# schematicEagle.net
KiCad netlist of a schematic drawn in EAGLE
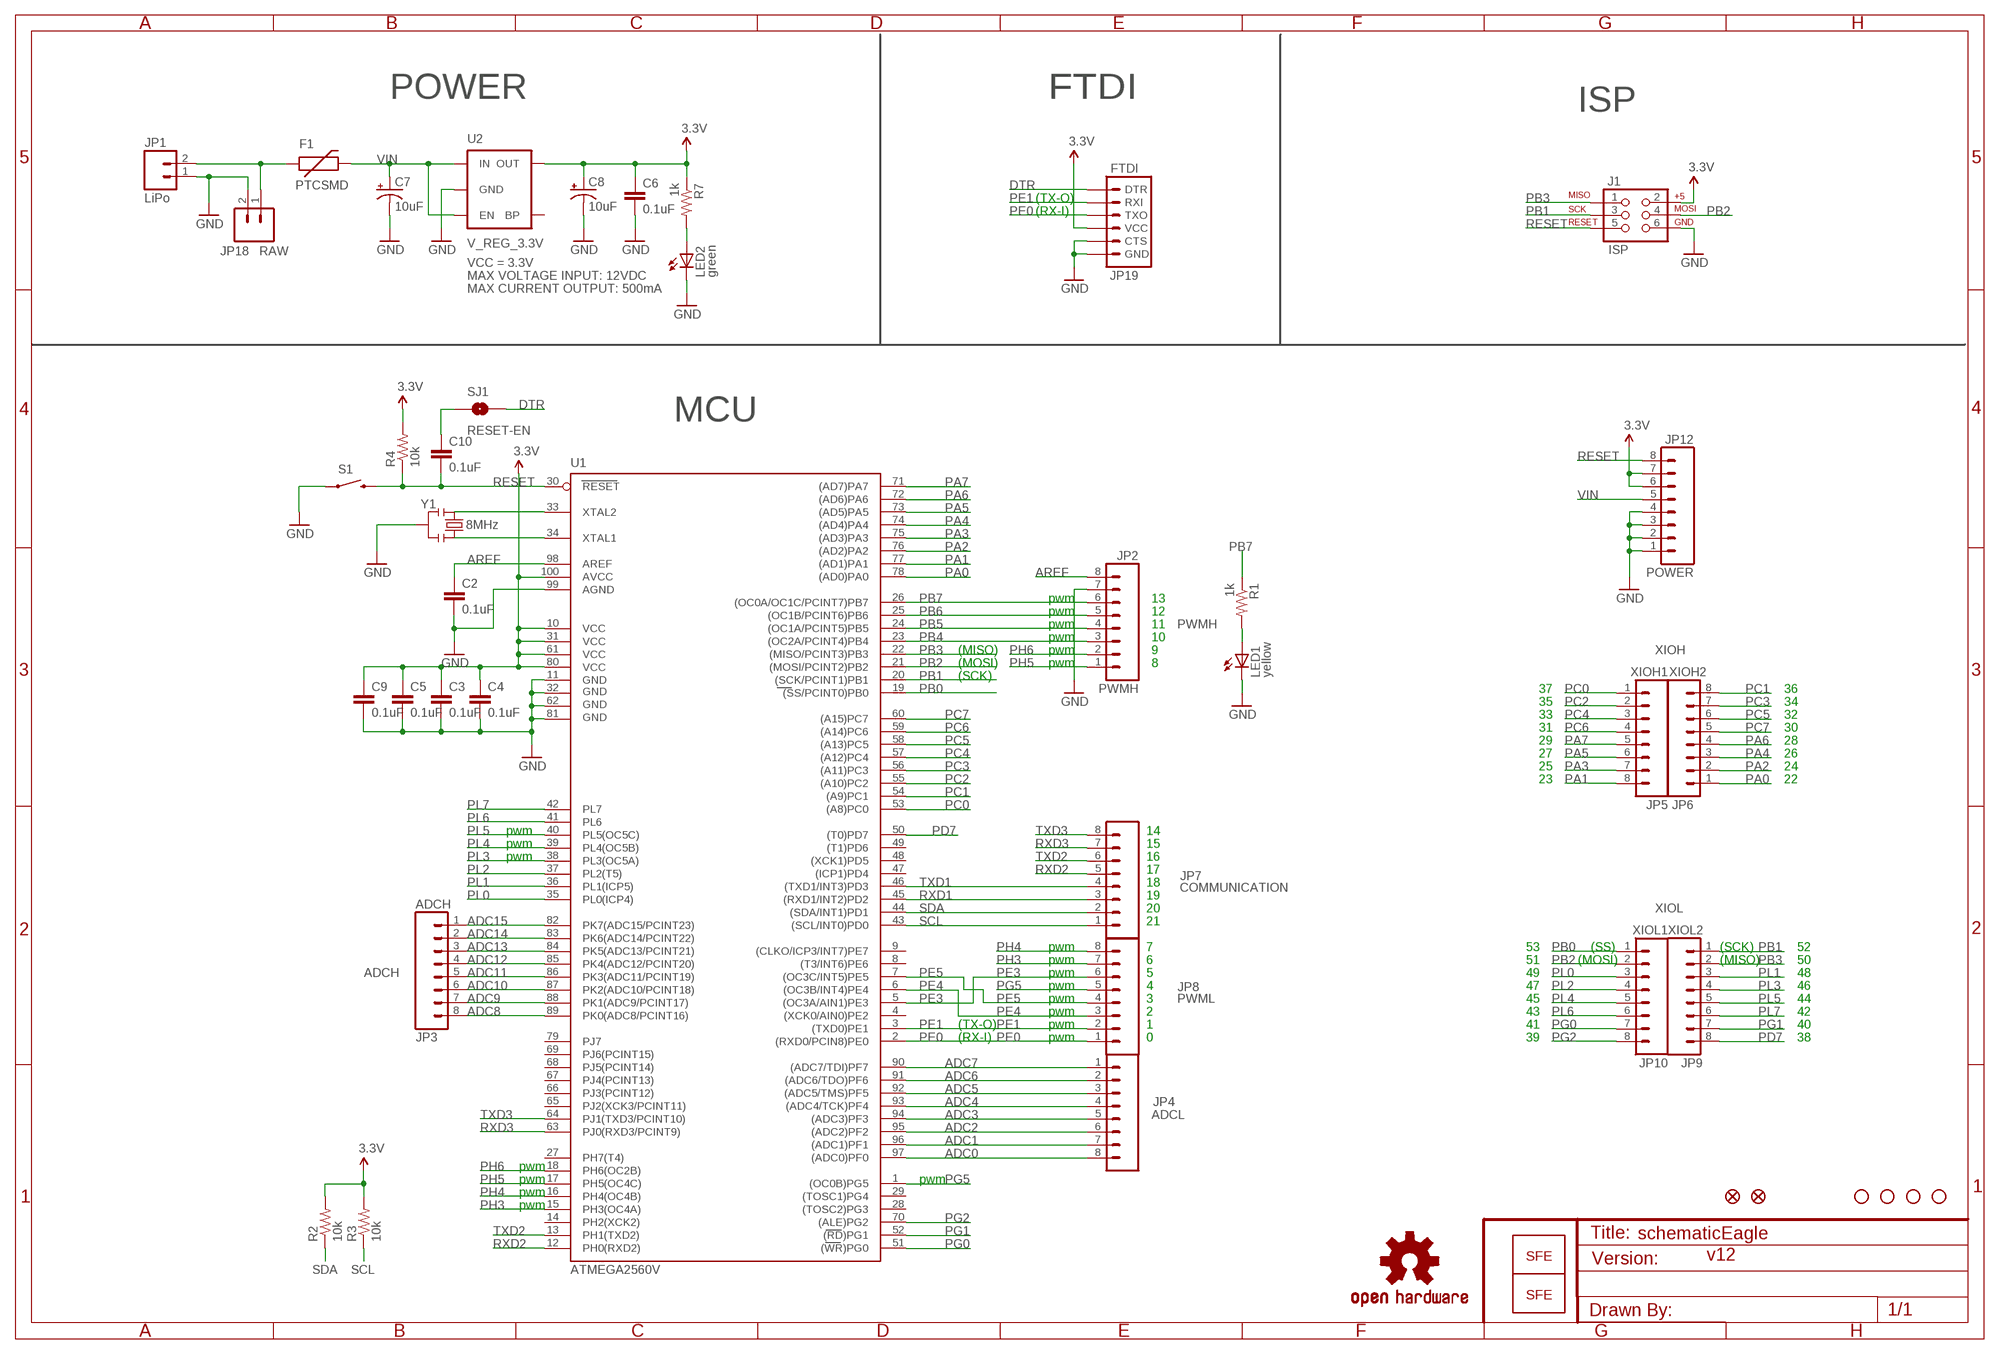
[diagram p0: schematic, sheet 1]

(export (version "E")
  (design (tool "Eeschema 10.0.6"))
  (components
    (comp (ref "C2")
      (value "0.1uF")
      (footprint "eagle-import:0402-CAP")
      (libsource (lib "eagle-import") (part "CAP0402-CAP"))
    )
    (comp (ref "C3")
      (value "0.1uF")
      (footprint "eagle-import:0402-CAP")
      (libsource (lib "eagle-import") (part "CAP0402-CAP"))
    )
    (comp (ref "C4")
      (value "0.1uF")
      (footprint "eagle-import:0402-CAP")
      (libsource (lib "eagle-import") (part "CAP0402-CAP"))
    )
    (comp (ref "C5")
      (value "0.1uF")
      (footprint "eagle-import:0402-CAP")
      (libsource (lib "eagle-import") (part "CAP0402-CAP"))
    )
    (comp (ref "C6")
      (value "0.1uF")
      (footprint "eagle-import:0402-CAP")
      (libsource (lib "eagle-import") (part "CAP0402-CAP"))
    )
    (comp (ref "C7")
      (value "10uF")
      (footprint "eagle-import:EIA3216")
      (libsource (lib "eagle-import") (part "CAP_POL1206"))
    )
    (comp (ref "C8")
      (value "10uF")
      (footprint "eagle-import:EIA3216")
      (libsource (lib "eagle-import") (part "CAP_POL1206"))
    )
    (comp (ref "C9")
      (value "0.1uF")
      (footprint "eagle-import:0402-CAP")
      (libsource (lib "eagle-import") (part "CAP0402-CAP"))
    )
    (comp (ref "C10")
      (value "0.1uF")
      (footprint "eagle-import:0402-CAP")
      (libsource (lib "eagle-import") (part "CAP0402-CAP"))
    )
    (comp (ref "F1")
      (value "PTCSMD")
      (footprint "eagle-import:PTC-1206")
      (libsource (lib "eagle-import") (part "PTCSMD"))
    )
    (comp (ref "J1")
      (value "ISP")
      (footprint "eagle-import:2X3")
      (libsource (lib "eagle-import") (part "AVR_SPI_PRG_6PTH"))
    )
    (comp (ref "JP1")
      (value "LiPo")
      (footprint "eagle-import:JST-2-SMD")
      (libsource (lib "eagle-import") (part "M02-JST-2MM-SMT"))
    )
    (comp (ref "JP2")
      (value "PWMH")
      (footprint "eagle-import:BM08B-SRSS-TB")
      (libsource (lib "eagle-import") (part "M08BM08B-SRSS-TB"))
    )
    (comp (ref "JP3")
      (value "ADCH")
      (footprint "eagle-import:BM08B-SRSS-TB")
      (libsource (lib "eagle-import") (part "M08BM08B-SRSS-TB"))
    )
    (comp (ref "JP4")
      (value "ADCL")
      (footprint "eagle-import:BM08B-SRSS-TB")
      (libsource (lib "eagle-import") (part "M08BM08B-SRSS-TB"))
    )
    (comp (ref "JP5")
      (value "XIOH1")
      (footprint "eagle-import:BM08B-SRSS-TB")
      (libsource (lib "eagle-import") (part "M08BM08B-SRSS-TB"))
    )
    (comp (ref "JP6")
      (value "XIOH2")
      (footprint "eagle-import:BM08B-SRSS-TB")
      (libsource (lib "eagle-import") (part "M08BM08B-SRSS-TB"))
    )
    (comp (ref "JP7")
      (value "COMM")
      (footprint "eagle-import:BM08B-SRSS-TB")
      (libsource (lib "eagle-import") (part "M08BM08B-SRSS-TB"))
    )
    (comp (ref "JP8")
      (value "PWML")
      (footprint "eagle-import:BM08B-SRSS-TB")
      (libsource (lib "eagle-import") (part "M08BM08B-SRSS-TB"))
    )
    (comp (ref "JP9")
      (value "XIOL2")
      (footprint "eagle-import:BM08B-SRSS-TB")
      (libsource (lib "eagle-import") (part "M08BM08B-SRSS-TB"))
    )
    (comp (ref "JP10")
      (value "XIOL1")
      (footprint "eagle-import:BM08B-SRSS-TB")
      (libsource (lib "eagle-import") (part "M08BM08B-SRSS-TB"))
    )
    (comp (ref "JP11")
      (value "STAND-OFF")
      (footprint "eagle-import:STAND-OFF")
      (libsource (lib "eagle-import") (part "STAND-OFF"))
    )
    (comp (ref "JP12")
      (value "POWER")
      (footprint "eagle-import:BM08B-SRSS-TB")
      (libsource (lib "eagle-import") (part "M08BM08B-SRSS-TB"))
    )
    (comp (ref "JP13")
      (value "STAND-OFF")
      (footprint "eagle-import:STAND-OFF")
      (libsource (lib "eagle-import") (part "STAND-OFF"))
    )
    (comp (ref "JP14")
      (value "STAND-OFF")
      (footprint "eagle-import:STAND-OFF")
      (libsource (lib "eagle-import") (part "STAND-OFF"))
    )
    (comp (ref "JP15")
      (value "STAND-OFF")
      (footprint "eagle-import:STAND-OFF")
      (libsource (lib "eagle-import") (part "STAND-OFF"))
    )
    (comp (ref "JP16")
      (value "LOGO-SFENEW")
      (footprint "eagle-import:SFE-NEW-WEBLOGO")
      (libsource (lib "eagle-import") (part "LOGO-SFENEW"))
    )
    (comp (ref "JP17")
      (value "LOGO-SFESK")
      (footprint "eagle-import:SFE-LOGO-FLAME")
      (libsource (lib "eagle-import") (part "LOGO-SFESK"))
    )
    (comp (ref "JP18")
      (value "RAW")
      (footprint "eagle-import:1X02")
      (libsource (lib "eagle-import") (part "M02PTH"))
    )
    (comp (ref "JP19")
      (value "FTDI")
      (footprint "eagle-import:1X06-SMD")
      (libsource (lib "eagle-import") (part "ARDUINO_SERIAL_PROGRAMSMD"))
    )
    (comp (ref "JP20")
      (value "FIDUCIAL1X2.5")
      (footprint "eagle-import:FIDUCIAL-1X2.5")
      (libsource (lib "eagle-import") (part "FIDUCIAL1X2.5"))
    )
    (comp (ref "JP21")
      (value "FIDUCIAL1X2.5")
      (footprint "eagle-import:FIDUCIAL-1X2.5")
      (libsource (lib "eagle-import") (part "FIDUCIAL1X2.5"))
    )
    (comp (ref "LED1")
      (value "yellow")
      (footprint "eagle-import:LED-0603")
      (libsource (lib "eagle-import") (part "LED0603"))
    )
    (comp (ref "LED2")
      (value "green")
      (footprint "eagle-import:LED-0603")
      (libsource (lib "eagle-import") (part "LED0603"))
    )
    (comp (ref "R1")
      (value "1k")
      (footprint "eagle-import:0402-RES")
      (libsource (lib "eagle-import") (part "RESISTOR0402-RES"))
    )
    (comp (ref "R2")
      (value "10k")
      (footprint "eagle-import:0402-RES")
      (libsource (lib "eagle-import") (part "RESISTOR0402-RES"))
    )
    (comp (ref "R3")
      (value "10k")
      (footprint "eagle-import:0402-RES")
      (libsource (lib "eagle-import") (part "RESISTOR0402-RES"))
    )
    (comp (ref "R4")
      (value "10k")
      (footprint "eagle-import:0402-RES")
      (libsource (lib "eagle-import") (part "RESISTOR0402-RES"))
    )
    (comp (ref "R7")
      (value "1k")
      (footprint "eagle-import:0402-RES")
      (libsource (lib "eagle-import") (part "RESISTOR0402-RES"))
    )
    (comp (ref "S1")
      (value "SWITCH-MOMENTARY-2SMD")
      (footprint "eagle-import:TACTILE_SWITCH_SMD")
      (libsource (lib "eagle-import") (part "SWITCH-MOMENTARY-2SMD"))
    )
    (comp (ref "SJ1")
      (value "RESET-EN")
      (footprint "eagle-import:SJ_2S")
      (libsource (lib "eagle-import") (part "SOLDERJUMPERNC"))
    )
    (comp (ref "U$9")
      (value "OSHW-LOGOL")
      (footprint "eagle-import:OSHW-LOGO-L")
      (libsource (lib "eagle-import") (part "OSHW-LOGOL"))
    )
    (comp (ref "U1")
      (value "ATMEGA2560AU")
      (footprint "eagle-import:TQFP100")
      (libsource (lib "eagle-import") (part "ATMEGA2560AU"))
    )
    (comp (ref "U2")
      (value "V_REG_3.3V")
      (footprint "eagle-import:SOT23-5")
      (libsource (lib "eagle-import") (part "V_REG_LDOSMD"))
    )
    (comp (ref "Y1")
      (value "RESONATORSMD")
      (footprint "eagle-import:RESONATOR-SMD")
      (libsource (lib "eagle-import") (part "RESONATORSMD"))
    )
  )
  (nets
    (net (code "1") (name "/ADC0") (class "Default")
      (node (ref "JP4") (pin "8") (pinfunction "8_8") (pintype "passive"))
      (node (ref "U1") (pin "97") (pinfunction "(ADC0)PF0_97") (pintype "bidirectional"))
    )
    (net (code "2") (name "/ADC1") (class "Default")
      (node (ref "JP4") (pin "7") (pinfunction "7_7") (pintype "passive"))
      (node (ref "U1") (pin "96") (pinfunction "(ADC1)PF1_96") (pintype "bidirectional"))
    )
    (net (code "3") (name "/ADC2") (class "Default")
      (node (ref "JP4") (pin "6") (pinfunction "6_6") (pintype "passive"))
      (node (ref "U1") (pin "95") (pinfunction "(ADC2)PF2_95") (pintype "bidirectional"))
    )
    (net (code "4") (name "/ADC3") (class "Default")
      (node (ref "JP4") (pin "5") (pinfunction "5_5") (pintype "passive"))
      (node (ref "U1") (pin "94") (pinfunction "(ADC3)PF3_94") (pintype "bidirectional"))
    )
    (net (code "5") (name "/ADC4") (class "Default")
      (node (ref "JP4") (pin "4") (pinfunction "4_4") (pintype "passive"))
      (node (ref "U1") (pin "93") (pinfunction "(ADC4/TCK)PF4_93") (pintype "bidirectional"))
    )
    (net (code "6") (name "/ADC5") (class "Default")
      (node (ref "JP4") (pin "3") (pinfunction "3_3") (pintype "passive"))
      (node (ref "U1") (pin "92") (pinfunction "(ADC5/TMS)PF5_92") (pintype "bidirectional"))
    )
    (net (code "7") (name "/ADC6") (class "Default")
      (node (ref "JP4") (pin "2") (pinfunction "2_2") (pintype "passive"))
      (node (ref "U1") (pin "91") (pinfunction "(ADC6/TDO)PF6_91") (pintype "bidirectional"))
    )
    (net (code "8") (name "/ADC7") (class "Default")
      (node (ref "JP4") (pin "1") (pinfunction "1_1") (pintype "passive"))
      (node (ref "U1") (pin "90") (pinfunction "(ADC7/TDI)PF7_90") (pintype "bidirectional"))
    )
    (net (code "9") (name "/ADC8") (class "Default")
      (node (ref "JP3") (pin "8") (pinfunction "8_8") (pintype "passive"))
      (node (ref "U1") (pin "89") (pinfunction "PK0(ADC8/PCINT16)_89") (pintype "bidirectional"))
    )
    (net (code "10") (name "/ADC9") (class "Default")
      (node (ref "JP3") (pin "7") (pinfunction "7_7") (pintype "passive"))
      (node (ref "U1") (pin "88") (pinfunction "PK1(ADC9/PCINT17)_88") (pintype "bidirectional"))
    )
    (net (code "11") (name "/ADC10") (class "Default")
      (node (ref "JP3") (pin "6") (pinfunction "6_6") (pintype "passive"))
      (node (ref "U1") (pin "87") (pinfunction "PK2(ADC10/PCINT18)_87") (pintype "bidirectional"))
    )
    (net (code "12") (name "/ADC11") (class "Default")
      (node (ref "JP3") (pin "5") (pinfunction "5_5") (pintype "passive"))
      (node (ref "U1") (pin "86") (pinfunction "PK3(ADC11/PCINT19)_86") (pintype "bidirectional"))
    )
    (net (code "13") (name "/ADC12") (class "Default")
      (node (ref "JP3") (pin "4") (pinfunction "4_4") (pintype "passive"))
      (node (ref "U1") (pin "85") (pinfunction "PK4(ADC12/PCINT20)_85") (pintype "bidirectional"))
    )
    (net (code "14") (name "/ADC13") (class "Default")
      (node (ref "JP3") (pin "3") (pinfunction "3_3") (pintype "passive"))
      (node (ref "U1") (pin "84") (pinfunction "PK5(ADC13/PCINT21)_84") (pintype "bidirectional"))
    )
    (net (code "15") (name "/ADC14") (class "Default")
      (node (ref "JP3") (pin "2") (pinfunction "2_2") (pintype "passive"))
      (node (ref "U1") (pin "83") (pinfunction "PK6(ADC14/PCINT22)_83") (pintype "bidirectional"))
    )
    (net (code "16") (name "/ADC15") (class "Default")
      (node (ref "JP3") (pin "1") (pinfunction "1_1") (pintype "passive"))
      (node (ref "U1") (pin "82") (pinfunction "PK7(ADC15/PCINT23)_82") (pintype "bidirectional"))
    )
    (net (code "17") (name "/AREF") (class "Default")
      (node (ref "C2") (pin "1") (pinfunction "1_1") (pintype "passive"))
      (node (ref "JP2") (pin "8") (pinfunction "8_8") (pintype "passive"))
      (node (ref "U1") (pin "98") (pinfunction "AREF_98") (pintype "bidirectional"))
    )
    (net (code "18") (name "/DTR") (class "Default")
      (node (ref "JP19") (pin "1") (pinfunction "DTR_1") (pintype "passive"))
      (node (ref "SJ1") (pin "2") (pinfunction "2_2") (pintype "passive"))
    )
    (net (code "19") (name "/PA0") (class "Default")
      (node (ref "JP6") (pin "1") (pinfunction "1_1") (pintype "passive"))
      (node (ref "U1") (pin "78") (pinfunction "(AD0)PA0_78") (pintype "bidirectional"))
    )
    (net (code "20") (name "/PA1") (class "Default")
      (node (ref "JP5") (pin "8") (pinfunction "8_8") (pintype "passive"))
      (node (ref "U1") (pin "77") (pinfunction "(AD1)PA1_77") (pintype "bidirectional"))
    )
    (net (code "21") (name "/PA2") (class "Default")
      (node (ref "JP6") (pin "2") (pinfunction "2_2") (pintype "passive"))
      (node (ref "U1") (pin "76") (pinfunction "(AD2)PA2_76") (pintype "bidirectional"))
    )
    (net (code "22") (name "/PA3") (class "Default")
      (node (ref "JP5") (pin "7") (pinfunction "7_7") (pintype "passive"))
      (node (ref "U1") (pin "75") (pinfunction "(AD3)PA3_75") (pintype "bidirectional"))
    )
    (net (code "23") (name "/PA4") (class "Default")
      (node (ref "JP6") (pin "3") (pinfunction "3_3") (pintype "passive"))
      (node (ref "U1") (pin "74") (pinfunction "(AD4)PA4_74") (pintype "bidirectional"))
    )
    (net (code "24") (name "/PA5") (class "Default")
      (node (ref "JP5") (pin "6") (pinfunction "6_6") (pintype "passive"))
      (node (ref "U1") (pin "73") (pinfunction "(AD5)PA5_73") (pintype "bidirectional"))
    )
    (net (code "25") (name "/PA6") (class "Default")
      (node (ref "JP6") (pin "4") (pinfunction "4_4") (pintype "passive"))
      (node (ref "U1") (pin "72") (pinfunction "(AD6)PA6_72") (pintype "bidirectional"))
    )
    (net (code "26") (name "/PA7") (class "Default")
      (node (ref "JP5") (pin "5") (pinfunction "5_5") (pintype "passive"))
      (node (ref "U1") (pin "71") (pinfunction "(AD7)PA7_71") (pintype "bidirectional"))
    )
    (net (code "27") (name "/PB0") (class "Default")
      (node (ref "JP10") (pin "1") (pinfunction "1_1") (pintype "passive"))
      (node (ref "U1") (pin "19") (pinfunction "(SS/PCINT0)PB0_19") (pintype "bidirectional"))
    )
    (net (code "28") (name "/PB1") (class "Default")
      (node (ref "J1") (pin "3") (pinfunction "3_3") (pintype "passive"))
      (node (ref "JP9") (pin "1") (pinfunction "1_1") (pintype "passive"))
      (node (ref "U1") (pin "20") (pinfunction "(SCK/PCINT1)PB1_20") (pintype "bidirectional"))
    )
    (net (code "29") (name "/PB2") (class "Default")
      (node (ref "J1") (pin "4") (pinfunction "4_4") (pintype "passive"))
      (node (ref "JP10") (pin "2") (pinfunction "2_2") (pintype "passive"))
      (node (ref "U1") (pin "21") (pinfunction "(MOSI/PCINT2)PB2_21") (pintype "bidirectional"))
    )
    (net (code "30") (name "/PB3") (class "Default")
      (node (ref "J1") (pin "1") (pinfunction "1_1") (pintype "passive"))
      (node (ref "JP9") (pin "2") (pinfunction "2_2") (pintype "passive"))
      (node (ref "U1") (pin "22") (pinfunction "(MISO/PCINT3)PB3_22") (pintype "bidirectional"))
    )
    (net (code "31") (name "/PB4") (class "Default")
      (node (ref "JP2") (pin "3") (pinfunction "3_3") (pintype "passive"))
      (node (ref "U1") (pin "23") (pinfunction "(OC2A/PCINT4)PB4_23") (pintype "bidirectional"))
    )
    (net (code "32") (name "/PB5") (class "Default")
      (node (ref "JP2") (pin "4") (pinfunction "4_4") (pintype "passive"))
      (node (ref "U1") (pin "24") (pinfunction "(OC1A/PCINT5)PB5_24") (pintype "bidirectional"))
    )
    (net (code "33") (name "/PB6") (class "Default")
      (node (ref "JP2") (pin "5") (pinfunction "5_5") (pintype "passive"))
      (node (ref "U1") (pin "25") (pinfunction "(OC1B/PCINT6)PB6_25") (pintype "bidirectional"))
    )
    (net (code "34") (name "/PB7") (class "Default")
      (node (ref "JP2") (pin "6") (pinfunction "6_6") (pintype "passive"))
      (node (ref "R1") (pin "1") (pinfunction "1_1") (pintype "passive"))
      (node (ref "U1") (pin "26") (pinfunction "(OC0A/OC1C/PCINT7)PB7_26") (pintype "bidirectional"))
    )
    (net (code "35") (name "/PC0") (class "Default")
      (node (ref "JP5") (pin "1") (pinfunction "1_1") (pintype "passive"))
      (node (ref "U1") (pin "53") (pinfunction "(A8)PC0_53") (pintype "bidirectional"))
    )
    (net (code "36") (name "/PC1") (class "Default")
      (node (ref "JP6") (pin "8") (pinfunction "8_8") (pintype "passive"))
      (node (ref "U1") (pin "54") (pinfunction "(A9)PC1_54") (pintype "bidirectional"))
    )
    (net (code "37") (name "/PC2") (class "Default")
      (node (ref "JP5") (pin "2") (pinfunction "2_2") (pintype "passive"))
      (node (ref "U1") (pin "55") (pinfunction "(A10)PC2_55") (pintype "bidirectional"))
    )
    (net (code "38") (name "/PC3") (class "Default")
      (node (ref "JP6") (pin "7") (pinfunction "7_7") (pintype "passive"))
      (node (ref "U1") (pin "56") (pinfunction "(A11)PC3_56") (pintype "bidirectional"))
    )
    (net (code "39") (name "/PC4") (class "Default")
      (node (ref "JP5") (pin "3") (pinfunction "3_3") (pintype "passive"))
      (node (ref "U1") (pin "57") (pinfunction "(A12)PC4_57") (pintype "bidirectional"))
    )
    (net (code "40") (name "/PC5") (class "Default")
      (node (ref "JP6") (pin "6") (pinfunction "6_6") (pintype "passive"))
      (node (ref "U1") (pin "58") (pinfunction "(A13)PC5_58") (pintype "bidirectional"))
    )
    (net (code "41") (name "/PC6") (class "Default")
      (node (ref "JP5") (pin "4") (pinfunction "4_4") (pintype "passive"))
      (node (ref "U1") (pin "59") (pinfunction "(A14)PC6_59") (pintype "bidirectional"))
    )
    (net (code "42") (name "/PC7") (class "Default")
      (node (ref "JP6") (pin "5") (pinfunction "5_5") (pintype "passive"))
      (node (ref "U1") (pin "60") (pinfunction "(A15)PC7_60") (pintype "bidirectional"))
    )
    (net (code "43") (name "/PD7") (class "Default")
      (node (ref "JP9") (pin "8") (pinfunction "8_8") (pintype "passive"))
      (node (ref "U1") (pin "50") (pinfunction "(T0)PD7_50") (pintype "bidirectional"))
    )
    (net (code "44") (name "/PE0") (class "Default")
      (node (ref "JP19") (pin "3") (pinfunction "TXO_3") (pintype "passive"))
      (node (ref "JP8") (pin "1") (pinfunction "1_1") (pintype "passive"))
      (node (ref "U1") (pin "2") (pinfunction "(RXD0/PCIN8)PE0_2") (pintype "bidirectional"))
    )
    (net (code "45") (name "/PE1") (class "Default")
      (node (ref "JP19") (pin "2") (pinfunction "RXI_2") (pintype "passive"))
      (node (ref "JP8") (pin "2") (pinfunction "2_2") (pintype "passive"))
      (node (ref "U1") (pin "3") (pinfunction "(TXD0)PE1_3") (pintype "bidirectional"))
    )
    (net (code "46") (name "/PE3") (class "Default")
      (node (ref "JP8") (pin "6") (pinfunction "6_6") (pintype "passive"))
      (node (ref "U1") (pin "5") (pinfunction "(OC3A/AIN1)PE3_5") (pintype "bidirectional"))
    )
    (net (code "47") (name "/PE4") (class "Default")
      (node (ref "JP8") (pin "3") (pinfunction "3_3") (pintype "passive"))
      (node (ref "U1") (pin "6") (pinfunction "(OC3B/INT4)PE4_6") (pintype "bidirectional"))
    )
    (net (code "48") (name "/PE5") (class "Default")
      (node (ref "JP8") (pin "4") (pinfunction "4_4") (pintype "passive"))
      (node (ref "U1") (pin "7") (pinfunction "(OC3C/INT5)PE5_7") (pintype "bidirectional"))
    )
    (net (code "49") (name "/PG0") (class "Default")
      (node (ref "JP10") (pin "7") (pinfunction "7_7") (pintype "passive"))
      (node (ref "U1") (pin "51") (pinfunction "(WR)PG0_51") (pintype "bidirectional"))
    )
    (net (code "50") (name "/PG1") (class "Default")
      (node (ref "JP9") (pin "7") (pinfunction "7_7") (pintype "passive"))
      (node (ref "U1") (pin "52") (pinfunction "(RD)PG1_52") (pintype "bidirectional"))
    )
    (net (code "51") (name "/PG2") (class "Default")
      (node (ref "JP10") (pin "8") (pinfunction "8_8") (pintype "passive"))
      (node (ref "U1") (pin "70") (pinfunction "(ALE)PG2_70") (pintype "bidirectional"))
    )
    (net (code "52") (name "/PG5") (class "Default")
      (node (ref "JP8") (pin "5") (pinfunction "5_5") (pintype "passive"))
      (node (ref "U1") (pin "1") (pinfunction "(OC0B)PG5_1") (pintype "bidirectional"))
    )
    (net (code "53") (name "/PH3") (class "Default")
      (node (ref "JP8") (pin "7") (pinfunction "7_7") (pintype "passive"))
      (node (ref "U1") (pin "15") (pinfunction "PH3(OC4A)_15") (pintype "bidirectional"))
    )
    (net (code "54") (name "/PH4") (class "Default")
      (node (ref "JP8") (pin "8") (pinfunction "8_8") (pintype "passive"))
      (node (ref "U1") (pin "16") (pinfunction "PH4(OC4B)_16") (pintype "bidirectional"))
    )
    (net (code "55") (name "/PH5") (class "Default")
      (node (ref "JP2") (pin "1") (pinfunction "1_1") (pintype "passive"))
      (node (ref "U1") (pin "17") (pinfunction "PH5(OC4C)_17") (pintype "bidirectional"))
    )
    (net (code "56") (name "/PH6") (class "Default")
      (node (ref "JP2") (pin "2") (pinfunction "2_2") (pintype "passive"))
      (node (ref "U1") (pin "18") (pinfunction "PH6(OC2B)_18") (pintype "bidirectional"))
    )
    (net (code "57") (name "/PL0") (class "Default")
      (node (ref "JP10") (pin "3") (pinfunction "3_3") (pintype "passive"))
      (node (ref "U1") (pin "35") (pinfunction "PL0(ICP4)_35") (pintype "bidirectional"))
    )
    (net (code "58") (name "/PL1") (class "Default")
      (node (ref "JP9") (pin "3") (pinfunction "3_3") (pintype "passive"))
      (node (ref "U1") (pin "36") (pinfunction "PL1(ICP5)_36") (pintype "bidirectional"))
    )
    (net (code "59") (name "/PL2") (class "Default")
      (node (ref "JP10") (pin "4") (pinfunction "4_4") (pintype "passive"))
      (node (ref "U1") (pin "37") (pinfunction "PL2(T5)_37") (pintype "bidirectional"))
    )
    (net (code "60") (name "/PL3") (class "Default")
      (node (ref "JP9") (pin "4") (pinfunction "4_4") (pintype "passive"))
      (node (ref "U1") (pin "38") (pinfunction "PL3(OC5A)_38") (pintype "bidirectional"))
    )
    (net (code "61") (name "/PL4") (class "Default")
      (node (ref "JP10") (pin "5") (pinfunction "5_5") (pintype "passive"))
      (node (ref "U1") (pin "39") (pinfunction "PL4(OC5B)_39") (pintype "bidirectional"))
    )
    (net (code "62") (name "/PL5") (class "Default")
      (node (ref "JP9") (pin "5") (pinfunction "5_5") (pintype "passive"))
      (node (ref "U1") (pin "40") (pinfunction "PL5(OC5C)_40") (pintype "bidirectional"))
    )
    (net (code "63") (name "/PL6") (class "Default")
      (node (ref "JP10") (pin "6") (pinfunction "6_6") (pintype "passive"))
      (node (ref "U1") (pin "41") (pinfunction "PL6_41") (pintype "bidirectional"))
    )
    (net (code "64") (name "/PL7") (class "Default")
      (node (ref "JP9") (pin "6") (pinfunction "6_6") (pintype "passive"))
      (node (ref "U1") (pin "42") (pinfunction "PL7_42") (pintype "bidirectional"))
    )
    (net (code "65") (name "/RESET") (class "Default")
      (node (ref "C10") (pin "2") (pinfunction "2_2") (pintype "passive"))
      (node (ref "J1") (pin "5") (pinfunction "5_5") (pintype "passive"))
      (node (ref "JP12") (pin "8") (pinfunction "8_8") (pintype "passive"))
      (node (ref "R4") (pin "1") (pinfunction "1_1") (pintype "passive"))
      (node (ref "S1") (pin "3") (pinfunction "2_3") (pintype "passive"))
      (node (ref "U1") (pin "30") (pinfunction "RESET_30") (pintype "input"))
    )
    (net (code "66") (name "/RXD1") (class "Default")
      (node (ref "JP7") (pin "3") (pinfunction "3_3") (pintype "passive"))
      (node (ref "U1") (pin "45") (pinfunction "(RXD1/INT2)PD2_45") (pintype "bidirectional"))
    )
    (net (code "67") (name "/RXD2") (class "Default")
      (node (ref "JP7") (pin "5") (pinfunction "5_5") (pintype "passive"))
      (node (ref "U1") (pin "12") (pinfunction "PH0(RXD2)_12") (pintype "bidirectional"))
    )
    (net (code "68") (name "/RXD3") (class "Default")
      (node (ref "JP7") (pin "7") (pinfunction "7_7") (pintype "passive"))
      (node (ref "U1") (pin "63") (pinfunction "PJ0(RXD3/PCINT9)_63") (pintype "bidirectional"))
    )
    (net (code "69") (name "/SCL") (class "Default")
      (node (ref "JP7") (pin "1") (pinfunction "1_1") (pintype "passive"))
      (node (ref "R3") (pin "1") (pinfunction "1_1") (pintype "passive"))
      (node (ref "U1") (pin "43") (pinfunction "(SCL/INT0)PD0_43") (pintype "bidirectional"))
    )
    (net (code "70") (name "/SDA") (class "Default")
      (node (ref "JP7") (pin "2") (pinfunction "2_2") (pintype "passive"))
      (node (ref "R2") (pin "1") (pinfunction "1_1") (pintype "passive"))
      (node (ref "U1") (pin "44") (pinfunction "(SDA/INT1)PD1_44") (pintype "bidirectional"))
    )
    (net (code "71") (name "/TXD1") (class "Default")
      (node (ref "JP7") (pin "4") (pinfunction "4_4") (pintype "passive"))
      (node (ref "U1") (pin "46") (pinfunction "(TXD1/INT3)PD3_46") (pintype "bidirectional"))
    )
    (net (code "72") (name "/TXD2") (class "Default")
      (node (ref "JP7") (pin "6") (pinfunction "6_6") (pintype "passive"))
      (node (ref "U1") (pin "13") (pinfunction "PH1(TXD2)_13") (pintype "bidirectional"))
    )
    (net (code "73") (name "/TXD3") (class "Default")
      (node (ref "JP7") (pin "8") (pinfunction "8_8") (pintype "passive"))
      (node (ref "U1") (pin "64") (pinfunction "PJ1(TXD3/PCINT10)_64") (pintype "bidirectional"))
    )
    (net (code "74") (name "/VIN") (class "Default")
      (node (ref "C7") (pin "A") (pinfunction "+_A") (pintype "passive"))
      (node (ref "F1") (pin "2") (pinfunction "2_2") (pintype "bidirectional"))
      (node (ref "JP12") (pin "5") (pinfunction "5_5") (pintype "passive"))
      (node (ref "U2") (pin "1") (pinfunction "IN_1") (pintype "input"))
      (node (ref "U2") (pin "3") (pinfunction "EN_3") (pintype "input"))
    )
    (net (code "75") (name "3.3V") (class "Default")
      (node (ref "C3") (pin "1") (pinfunction "1_1") (pintype "passive"))
      (node (ref "C4") (pin "1") (pinfunction "1_1") (pintype "passive"))
      (node (ref "C5") (pin "1") (pinfunction "1_1") (pintype "passive"))
      (node (ref "C6") (pin "1") (pinfunction "1_1") (pintype "passive"))
      (node (ref "C8") (pin "A") (pinfunction "+_A") (pintype "passive"))
      (node (ref "C9") (pin "1") (pinfunction "1_1") (pintype "passive"))
      (node (ref "J1") (pin "2") (pinfunction "2_2") (pintype "passive"))
      (node (ref "JP12") (pin "6") (pinfunction "6_6") (pintype "passive"))
      (node (ref "JP12") (pin "7") (pinfunction "7_7") (pintype "passive"))
      (node (ref "JP19") (pin "4") (pinfunction "VCC_4") (pintype "passive"))
      (node (ref "R2") (pin "2") (pinfunction "2_2") (pintype "passive"))
      (node (ref "R3") (pin "2") (pinfunction "2_2") (pintype "passive"))
      (node (ref "R4") (pin "2") (pinfunction "2_2") (pintype "passive"))
      (node (ref "R7") (pin "1") (pinfunction "1_1") (pintype "passive"))
      (node (ref "U1") (pin "10") (pinfunction "VCC_10") (pintype "power_in"))
      (node (ref "U1") (pin "100") (pinfunction "AVCC_100") (pintype "power_in"))
      (node (ref "U1") (pin "31") (pinfunction "VCC1_31") (pintype "power_in"))
      (node (ref "U1") (pin "61") (pinfunction "VCC2_61") (pintype "power_in"))
      (node (ref "U1") (pin "80") (pinfunction "VCC3_80") (pintype "power_in"))
      (node (ref "U2") (pin "5") (pinfunction "OUT_5") (pintype "passive"))
    )
    (net (code "76") (name "GND") (class "Default")
      (node (ref "C2") (pin "2") (pinfunction "2_2") (pintype "passive"))
      (node (ref "C3") (pin "2") (pinfunction "2_2") (pintype "passive"))
      (node (ref "C4") (pin "2") (pinfunction "2_2") (pintype "passive"))
      (node (ref "C5") (pin "2") (pinfunction "2_2") (pintype "passive"))
      (node (ref "C6") (pin "2") (pinfunction "2_2") (pintype "passive"))
      (node (ref "C7") (pin "C") (pinfunction "-_C") (pintype "passive"))
      (node (ref "C8") (pin "C") (pinfunction "-_C") (pintype "passive"))
      (node (ref "C9") (pin "2") (pinfunction "2_2") (pintype "passive"))
      (node (ref "J1") (pin "6") (pinfunction "6_6") (pintype "passive"))
      (node (ref "JP1") (pin "1") (pinfunction "1_1") (pintype "passive"))
      (node (ref "JP12") (pin "1") (pinfunction "1_1") (pintype "passive"))
      (node (ref "JP12") (pin "2") (pinfunction "2_2") (pintype "passive"))
      (node (ref "JP12") (pin "3") (pinfunction "3_3") (pintype "passive"))
      (node (ref "JP12") (pin "4") (pinfunction "4_4") (pintype "passive"))
      (node (ref "JP18") (pin "2") (pinfunction "2_2") (pintype "passive"))
      (node (ref "JP19") (pin "5") (pinfunction "CTS_5") (pintype "passive"))
      (node (ref "JP19") (pin "6") (pinfunction "GND_6") (pintype "passive"))
      (node (ref "JP2") (pin "7") (pinfunction "7_7") (pintype "passive"))
      (node (ref "LED1") (pin "C") (pinfunction "C_C") (pintype "passive"))
      (node (ref "LED2") (pin "C") (pinfunction "C_C") (pintype "passive"))
      (node (ref "S1") (pin "1") (pinfunction "1_1") (pintype "passive"))
      (node (ref "U1") (pin "11") (pinfunction "GND_11") (pintype "power_in"))
      (node (ref "U1") (pin "32") (pinfunction "GND1_32") (pintype "power_in"))
      (node (ref "U1") (pin "62") (pinfunction "GND2_62") (pintype "power_in"))
      (node (ref "U1") (pin "81") (pinfunction "GND3_81") (pintype "power_in"))
      (node (ref "U1") (pin "99") (pinfunction "AGND_99") (pintype "power_in"))
      (node (ref "U2") (pin "2") (pinfunction "GND_2") (pintype "input"))
      (node (ref "Y1") (pin "2") (pinfunction "2_2") (pintype "passive"))
    )
    (net (code "77") (name "Net-(C10-Pad1)") (class "Default")
      (node (ref "C10") (pin "1") (pinfunction "1_1") (pintype "passive"))
      (node (ref "SJ1") (pin "1") (pinfunction "1_1") (pintype "passive"))
    )
    (net (code "78") (name "Net-(F1-Pad1)") (class "Default")
      (node (ref "F1") (pin "1") (pinfunction "1_1") (pintype "bidirectional"))
      (node (ref "JP1") (pin "2") (pinfunction "2_2") (pintype "passive"))
      (node (ref "JP18") (pin "1") (pinfunction "1_1") (pintype "passive"))
    )
    (net (code "79") (name "Net-(LED1-PadA)") (class "Default")
      (node (ref "LED1") (pin "A") (pinfunction "A_A") (pintype "passive"))
      (node (ref "R1") (pin "2") (pinfunction "2_2") (pintype "passive"))
    )
    (net (code "80") (name "Net-(LED2-PadA)") (class "Default")
      (node (ref "LED2") (pin "A") (pinfunction "A_A") (pintype "passive"))
      (node (ref "R7") (pin "2") (pinfunction "2_2") (pintype "passive"))
    )
    (net (code "81") (name "Net-(U1-XTAL1)") (class "Default")
      (node (ref "U1") (pin "34") (pinfunction "XTAL1_34") (pintype "input"))
      (node (ref "Y1") (pin "3") (pinfunction "3_3") (pintype "passive"))
    )
    (net (code "82") (name "Net-(U1-XTAL2)") (class "Default")
      (node (ref "U1") (pin "33") (pinfunction "XTAL2_33") (pintype "output"))
      (node (ref "Y1") (pin "1") (pinfunction "1_1") (pintype "passive"))
    )
    (net (code "83") (name "unconnected-(U1-(CLKO{slash}ICP3{slash}INT7)PE7-Pad9)") (class "Default")
      (node (ref "U1") (pin "9") (pinfunction "(CLKO/ICP3/INT7)PE7_9") (pintype "bidirectional"))
    )
    (net (code "84") (name "unconnected-(U1-(ICP1)PD4-Pad47)") (class "Default")
      (node (ref "U1") (pin "47") (pinfunction "(ICP1)PD4_47") (pintype "bidirectional"))
    )
    (net (code "85") (name "unconnected-(U1-(T1)PD6-Pad49)") (class "Default")
      (node (ref "U1") (pin "49") (pinfunction "(T1)PD6_49") (pintype "bidirectional"))
    )
    (net (code "86") (name "unconnected-(U1-(T3{slash}INT6)PE6-Pad8)") (class "Default")
      (node (ref "U1") (pin "8") (pinfunction "(T3/INT6)PE6_8") (pintype "bidirectional"))
    )
    (net (code "87") (name "unconnected-(U1-(TOSC1)PG4-Pad29)") (class "Default")
      (node (ref "U1") (pin "29") (pinfunction "(TOSC1)PG4_29") (pintype "bidirectional"))
    )
    (net (code "88") (name "unconnected-(U1-(TOSC2)PG3-Pad28)") (class "Default")
      (node (ref "U1") (pin "28") (pinfunction "(TOSC2)PG3_28") (pintype "bidirectional"))
    )
    (net (code "89") (name "unconnected-(U1-(XCK0{slash}AIN0)PE2-Pad4)") (class "Default")
      (node (ref "U1") (pin "4") (pinfunction "(XCK0/AIN0)PE2_4") (pintype "bidirectional"))
    )
    (net (code "90") (name "unconnected-(U1-(XCK1)PD5-Pad48)") (class "Default")
      (node (ref "U1") (pin "48") (pinfunction "(XCK1)PD5_48") (pintype "bidirectional"))
    )
    (net (code "91") (name "unconnected-(U1-PH2(XCK2)-Pad14)") (class "Default")
      (node (ref "U1") (pin "14") (pinfunction "PH2(XCK2)_14") (pintype "bidirectional"))
    )
    (net (code "92") (name "unconnected-(U1-PH7(T4)-Pad27)") (class "Default")
      (node (ref "U1") (pin "27") (pinfunction "PH7(T4)_27") (pintype "bidirectional"))
    )
    (net (code "93") (name "unconnected-(U1-PJ2(XCK3{slash}PCINT11)-Pad65)") (class "Default")
      (node (ref "U1") (pin "65") (pinfunction "PJ2(XCK3/PCINT11)_65") (pintype "bidirectional"))
    )
    (net (code "94") (name "unconnected-(U1-PJ3(PCINT12)-Pad66)") (class "Default")
      (node (ref "U1") (pin "66") (pinfunction "PJ3(PCINT12)_66") (pintype "bidirectional"))
    )
    (net (code "95") (name "unconnected-(U1-PJ4(PCINT13)-Pad67)") (class "Default")
      (node (ref "U1") (pin "67") (pinfunction "PJ4(PCINT13)_67") (pintype "bidirectional"))
    )
    (net (code "96") (name "unconnected-(U1-PJ5(PCINT14)-Pad68)") (class "Default")
      (node (ref "U1") (pin "68") (pinfunction "PJ5(PCINT14)_68") (pintype "bidirectional"))
    )
    (net (code "97") (name "unconnected-(U1-PJ6(PCINT15)-Pad69)") (class "Default")
      (node (ref "U1") (pin "69") (pinfunction "PJ6(PCINT15)_69") (pintype "bidirectional"))
    )
    (net (code "98") (name "unconnected-(U1-PJ7-Pad79)") (class "Default")
      (node (ref "U1") (pin "79") (pinfunction "PJ7_79") (pintype "bidirectional"))
    )
    (net (code "99") (name "unconnected-(U2-BP-Pad4)") (class "Default")
      (node (ref "U2") (pin "4") (pinfunction "BP_4") (pintype "input"))
    )
  )
)
